# 6-User_IO.net
KiCad netlist of a schematic drawn in Altium Designer
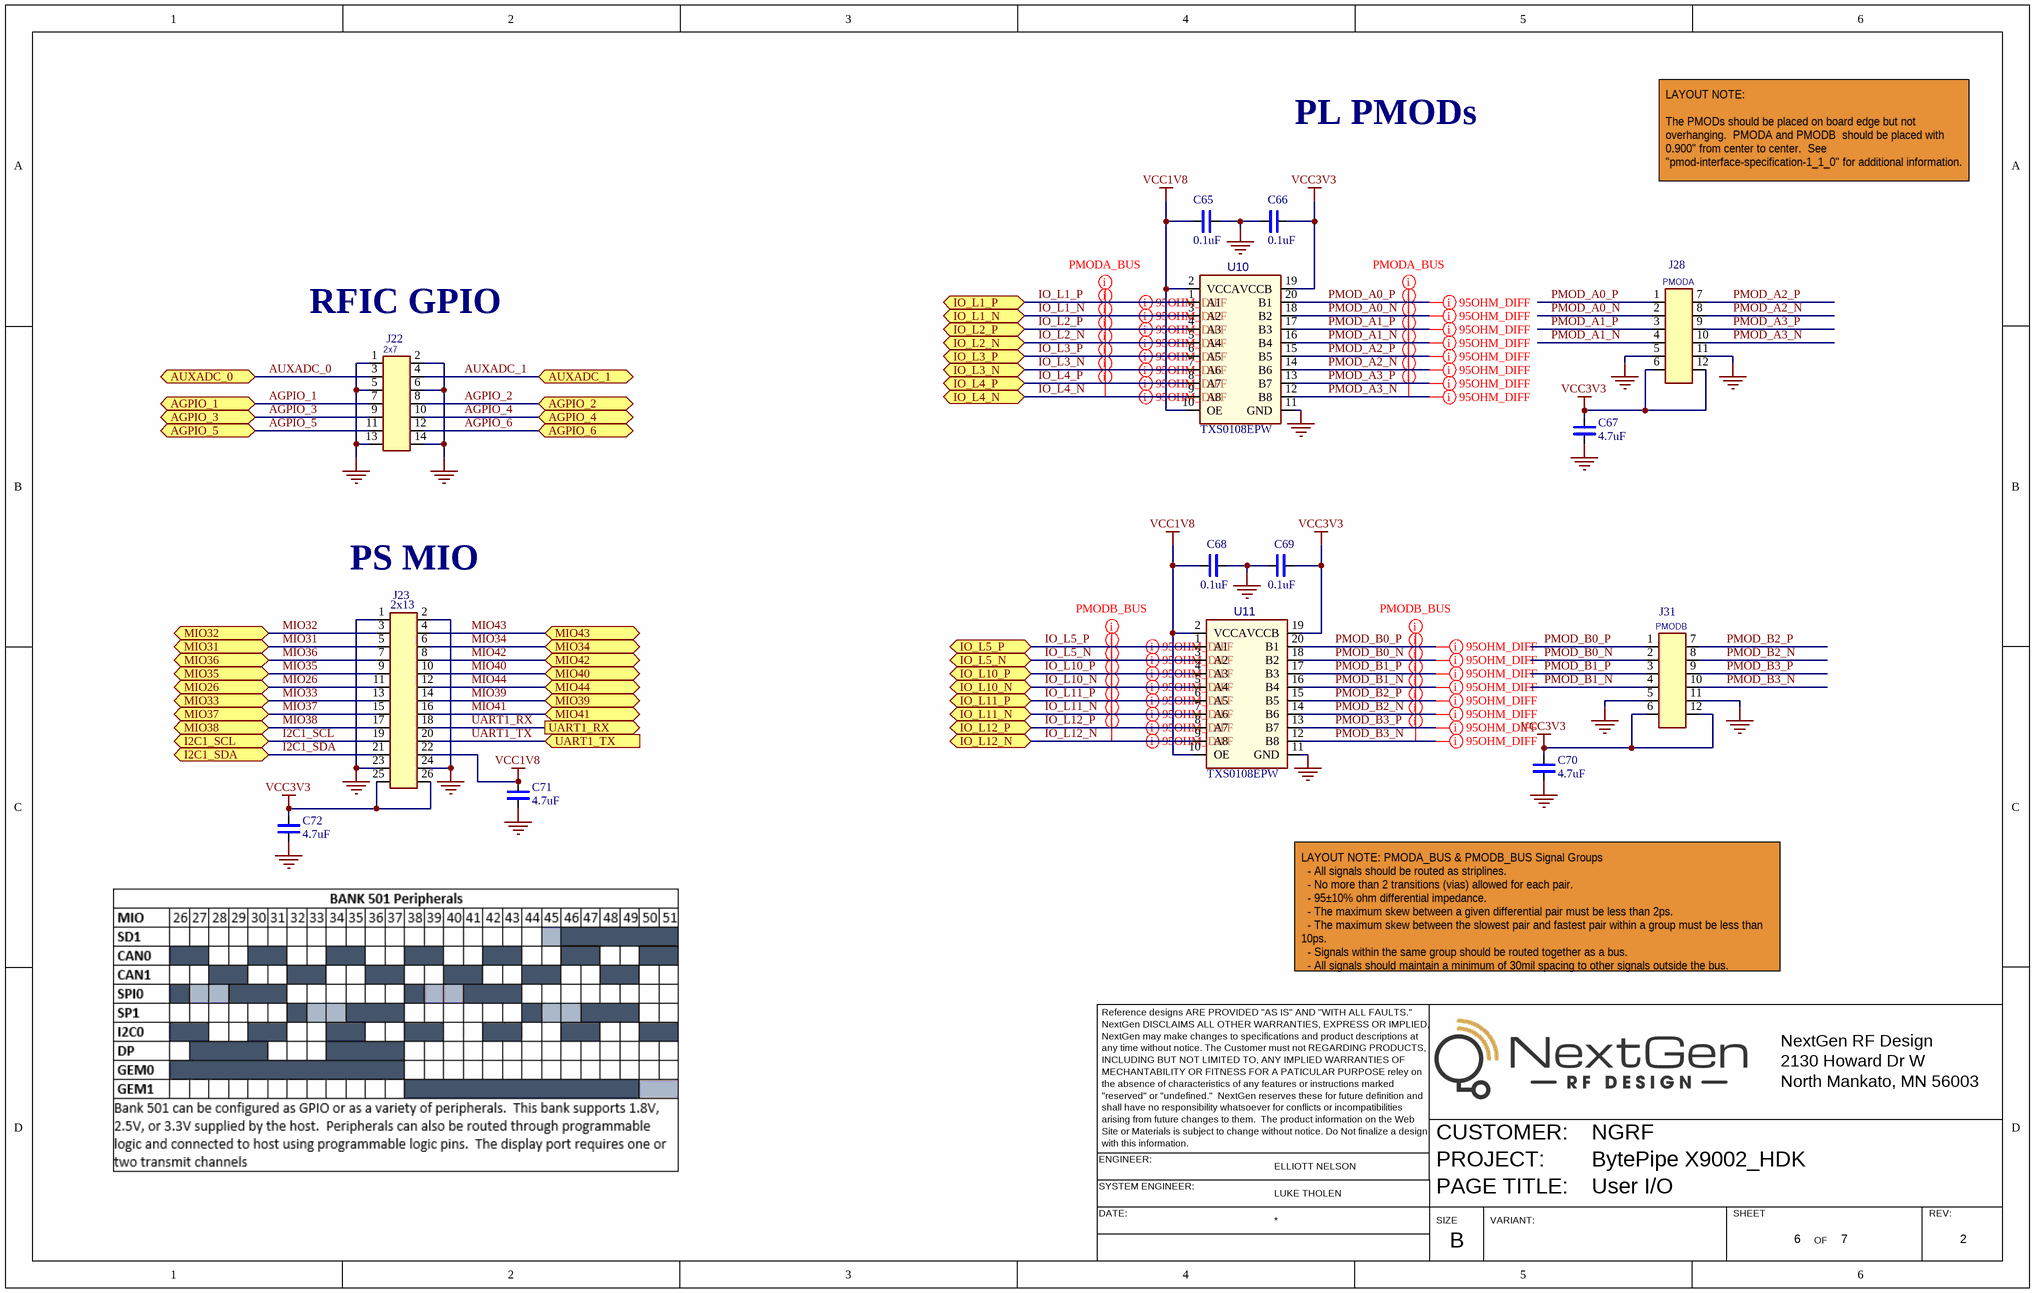
[diagram p0: 6-User IO.SchDoc]

(export (version "E")
  (design (tool "Eeschema 10.0.6"))
  (components
    (comp (ref "C65")
      (value "0.1uF")
      (footprint "SM/0402/CAP")
      (description "CAP CER 0.1UF 25V X7R 0402")
      (fields (field (name "Comment") "CAP_CERAMIC_0402"))
      (libsource (lib "NextGenRF_Symbols_SMT") (part "CAP_CERAMIC_0402"))
    )
    (comp (ref "C66")
      (value "0.1uF")
      (footprint "SM/0402/CAP")
      (description "CAP CER 0.1UF 25V X7R 0402")
      (fields (field (name "Comment") "CAP_CERAMIC_0402"))
      (libsource (lib "NextGenRF_Symbols_SMT") (part "CAP_CERAMIC_0402"))
    )
    (comp (ref "C67")
      (value "4.7uF")
      (footprint "SM/0402/CAP")
      (description "CAP CER 4.7UF 10V X5R 0402")
      (fields (field (name "Comment") "CAP_CERAMIC_0402"))
      (libsource (lib "NextGenRF_Symbols_SMT") (part "CAP_CERAMIC_0402"))
    )
    (comp (ref "C68")
      (value "0.1uF")
      (footprint "SM/0402/CAP")
      (description "CAP CER 0.1UF 25V X7R 0402")
      (fields (field (name "Comment") "CAP_CERAMIC_0402"))
      (libsource (lib "NextGenRF_Symbols_SMT") (part "CAP_CERAMIC_0402"))
    )
    (comp (ref "C69")
      (value "0.1uF")
      (footprint "SM/0402/CAP")
      (description "CAP CER 0.1UF 25V X7R 0402")
      (fields (field (name "Comment") "CAP_CERAMIC_0402"))
      (libsource (lib "NextGenRF_Symbols_SMT") (part "CAP_CERAMIC_0402"))
    )
    (comp (ref "C70")
      (value "4.7uF")
      (footprint "SM/0402/CAP")
      (description "CAP CER 4.7UF 10V X5R 0402")
      (fields (field (name "Comment") "CAP_CERAMIC_0402"))
      (libsource (lib "NextGenRF_Symbols_SMT") (part "CAP_CERAMIC_0402"))
    )
    (comp (ref "C71")
      (value "4.7uF")
      (footprint "SM/0402/CAP")
      (description "CAP CER 4.7UF 10V X5R 0402")
      (fields (field (name "Comment") "CAP_CERAMIC_0402"))
      (libsource (lib "NextGenRF_Symbols_SMT") (part "CAP_CERAMIC_0402"))
    )
    (comp (ref "C72")
      (value "4.7uF")
      (footprint "SM/0402/CAP")
      (description "CAP CER 4.7UF 10V X5R 0402")
      (fields (field (name "Comment") "CAP_CERAMIC_0402"))
      (libsource (lib "NextGenRF_Symbols_SMT") (part "CAP_CERAMIC_0402"))
    )
    (comp (ref "J22")
      (value "2x7")
      (footprint "CON/100SP/2X7P/VT/038_A")
      (description "Connector Header Through Hole 14 position 0.100\" (2.54mm)")
      (fields (field (name "Comment") "CON_100SP_2X7P_VT"))
      (libsource (lib "NextGenRF_Symbols_TH") (part "CON_100SP_2X7P_VT"))
    )
    (comp (ref "J23")
      (value "2x13")
      (footprint "NGRF_Thru-Hole_Footprints:CON/100SP/2X13P/038_A")
      (description "PIN HEADER, DOUBLE ROW 26 PIN, S")
      (fields (field (name "Comment") "CON_100SP_2X13P_VERT"))
      (libsource (lib "NextGenRF_Symbols_TH") (part "CON_100SP_2X13P_VERT"))
    )
    (comp (ref "J28")
      (value "PMODA")
      (footprint "CON/SAMTEC/SSW/2X6/RA_A/PMOD")
      (description "Header, 100 mil, 2x6, Right Angle, PMOD pin out.")
      (fields (field (name "Comment") "CON_100SP_2X6P_RA_PMOD"))
      (libsource (lib "NextGenRF_Symbols_TH") (part "CON_100SP_2X6P_RA_PMOD"))
    )
    (comp (ref "J31")
      (value "PMODB")
      (footprint "CON/SAMTEC/SSW/2X6/RA_A/PMOD")
      (description "Header, 100 mil, 2x6, Right Angle, PMOD pin out.")
      (fields (field (name "Comment") "CON_100SP_2X6P_RA_PMOD"))
      (libsource (lib "NextGenRF_Symbols_TH") (part "CON_100SP_2X6P_RA_PMOD"))
    )
    (comp (ref "U10")
      (value "TXS0108EPW")
      (footprint "SM/TSSOP20_6.5X6.4MM")
      (description "IC TRNSLTR BIDIRECTIONAL 20VQFN")
      (fields (field (name "Comment") "IC_TXS0108_TSSOP-20"))
      (libsource (lib "NextGenRF_Symbols_SMT") (part "IC_TXS0108_TSSOP-20"))
    )
    (comp (ref "U11")
      (value "TXS0108EPW")
      (footprint "SM/TSSOP20_6.5X6.4MM")
      (description "IC TRNSLTR BIDIRECTIONAL 20VQFN")
      (fields (field (name "Comment") "IC_TXS0108_TSSOP-20"))
      (libsource (lib "NextGenRF_Symbols_SMT") (part "IC_TXS0108_TSSOP-20"))
    )
  )
  (nets
    (net (code "1") (name "/AGPIO_1") (class "Default")
      (node (ref "J22") (pin "7") (pinfunction "N7_7") (pintype "passive"))
    )
    (net (code "2") (name "/AGPIO_2") (class "Default")
      (node (ref "J22") (pin "8") (pinfunction "N8_8") (pintype "passive"))
    )
    (net (code "3") (name "/AGPIO_3") (class "Default")
      (node (ref "J22") (pin "9") (pinfunction "N9_9") (pintype "passive"))
    )
    (net (code "4") (name "/AGPIO_4") (class "Default")
      (node (ref "J22") (pin "10") (pinfunction "N10_10") (pintype "passive"))
    )
    (net (code "5") (name "/AGPIO_5") (class "Default")
      (node (ref "J22") (pin "11") (pinfunction "N11_11") (pintype "passive"))
    )
    (net (code "6") (name "/AGPIO_6") (class "Default")
      (node (ref "J22") (pin "12") (pinfunction "N12_12") (pintype "passive"))
    )
    (net (code "7") (name "/AUXADC_0") (class "Default")
      (node (ref "J22") (pin "3") (pinfunction "N3_3") (pintype "passive"))
    )
    (net (code "8") (name "/AUXADC_1") (class "Default")
      (node (ref "J22") (pin "4") (pinfunction "N4_4") (pintype "passive"))
    )
    (net (code "9") (name "/I2C1_SCL") (class "Default")
      (node (ref "J23") (pin "19") (pinfunction "N19_19") (pintype "passive"))
    )
    (net (code "10") (name "/I2C1_SDA") (class "Default")
      (node (ref "J23") (pin "21") (pinfunction "N21_21") (pintype "passive"))
    )
    (net (code "11") (name "/IO_L1_N") (class "Default")
      (node (ref "U10") (pin "3") (pinfunction "A2_3") (pintype "passive"))
    )
    (net (code "12") (name "/IO_L1_P") (class "Default")
      (node (ref "U10") (pin "1") (pinfunction "A1_1") (pintype "passive"))
    )
    (net (code "13") (name "/IO_L2_N") (class "Default")
      (node (ref "U10") (pin "5") (pinfunction "A4_5") (pintype "passive"))
    )
    (net (code "14") (name "/IO_L2_P") (class "Default")
      (node (ref "U10") (pin "4") (pinfunction "A3_4") (pintype "passive"))
    )
    (net (code "15") (name "/IO_L3_N") (class "Default")
      (node (ref "U10") (pin "7") (pinfunction "A6_7") (pintype "passive"))
    )
    (net (code "16") (name "/IO_L3_P") (class "Default")
      (node (ref "U10") (pin "6") (pinfunction "A5_6") (pintype "passive"))
    )
    (net (code "17") (name "/IO_L4_N") (class "Default")
      (node (ref "U10") (pin "9") (pinfunction "A8_9") (pintype "passive"))
    )
    (net (code "18") (name "/IO_L4_P") (class "Default")
      (node (ref "U10") (pin "8") (pinfunction "A7_8") (pintype "passive"))
    )
    (net (code "19") (name "/IO_L5_N") (class "Default")
      (node (ref "U11") (pin "3") (pinfunction "A2_3") (pintype "passive"))
    )
    (net (code "20") (name "/IO_L5_P") (class "Default")
      (node (ref "U11") (pin "1") (pinfunction "A1_1") (pintype "passive"))
    )
    (net (code "21") (name "/IO_L10_N") (class "Default")
      (node (ref "U11") (pin "5") (pinfunction "A4_5") (pintype "passive"))
    )
    (net (code "22") (name "/IO_L10_P") (class "Default")
      (node (ref "U11") (pin "4") (pinfunction "A3_4") (pintype "passive"))
    )
    (net (code "23") (name "/IO_L11_N") (class "Default")
      (node (ref "U11") (pin "7") (pinfunction "A6_7") (pintype "passive"))
    )
    (net (code "24") (name "/IO_L11_P") (class "Default")
      (node (ref "U11") (pin "6") (pinfunction "A5_6") (pintype "passive"))
    )
    (net (code "25") (name "/IO_L12_N") (class "Default")
      (node (ref "U11") (pin "9") (pinfunction "A8_9") (pintype "passive"))
    )
    (net (code "26") (name "/IO_L12_P") (class "Default")
      (node (ref "U11") (pin "8") (pinfunction "A7_8") (pintype "passive"))
    )
    (net (code "27") (name "/MIO26") (class "Default")
      (node (ref "J23") (pin "11") (pinfunction "N11_11") (pintype "passive"))
    )
    (net (code "28") (name "/MIO31") (class "Default")
      (node (ref "J23") (pin "5") (pinfunction "N5_5") (pintype "passive"))
    )
    (net (code "29") (name "/MIO32") (class "Default")
      (node (ref "J23") (pin "3") (pinfunction "N3_3") (pintype "passive"))
    )
    (net (code "30") (name "/MIO33") (class "Default")
      (node (ref "J23") (pin "13") (pinfunction "N13_13") (pintype "passive"))
    )
    (net (code "31") (name "/MIO34") (class "Default")
      (node (ref "J23") (pin "6") (pinfunction "N6_6") (pintype "passive"))
    )
    (net (code "32") (name "/MIO35") (class "Default")
      (node (ref "J23") (pin "9") (pinfunction "N9_9") (pintype "passive"))
    )
    (net (code "33") (name "/MIO36") (class "Default")
      (node (ref "J23") (pin "7") (pinfunction "N7_7") (pintype "passive"))
    )
    (net (code "34") (name "/MIO37") (class "Default")
      (node (ref "J23") (pin "15") (pinfunction "N15_15") (pintype "passive"))
    )
    (net (code "35") (name "/MIO38") (class "Default")
      (node (ref "J23") (pin "17") (pinfunction "N17_17") (pintype "passive"))
    )
    (net (code "36") (name "/MIO39") (class "Default")
      (node (ref "J23") (pin "14") (pinfunction "N14_14") (pintype "passive"))
    )
    (net (code "37") (name "/MIO40") (class "Default")
      (node (ref "J23") (pin "10") (pinfunction "N10_10") (pintype "passive"))
    )
    (net (code "38") (name "/MIO41") (class "Default")
      (node (ref "J23") (pin "16") (pinfunction "N16_16") (pintype "passive"))
    )
    (net (code "39") (name "/MIO42") (class "Default")
      (node (ref "J23") (pin "8") (pinfunction "N8_8") (pintype "passive"))
    )
    (net (code "40") (name "/MIO43") (class "Default")
      (node (ref "J23") (pin "4") (pinfunction "N4_4") (pintype "passive"))
    )
    (net (code "41") (name "/MIO44") (class "Default")
      (node (ref "J23") (pin "12") (pinfunction "N12_12") (pintype "passive"))
    )
    (net (code "42") (name "/PMOD_A0_N") (class "Default")
      (node (ref "J28") (pin "2") (pinfunction "N2_2") (pintype "passive"))
      (node (ref "U10") (pin "18") (pinfunction "B2_18") (pintype "passive"))
    )
    (net (code "43") (name "/PMOD_A0_P") (class "Default")
      (node (ref "J28") (pin "1") (pinfunction "N1_1") (pintype "passive"))
      (node (ref "U10") (pin "20") (pinfunction "B1_20") (pintype "passive"))
    )
    (net (code "44") (name "/PMOD_A1_N") (class "Default")
      (node (ref "J28") (pin "4") (pinfunction "N4_4") (pintype "passive"))
      (node (ref "U10") (pin "16") (pinfunction "B4_16") (pintype "passive"))
    )
    (net (code "45") (name "/PMOD_A1_P") (class "Default")
      (node (ref "J28") (pin "3") (pinfunction "N3_3") (pintype "passive"))
      (node (ref "U10") (pin "17") (pinfunction "B3_17") (pintype "passive"))
    )
    (net (code "46") (name "/PMOD_A2_N") (class "Default")
      (node (ref "J28") (pin "8") (pinfunction "N8_8") (pintype "passive"))
      (node (ref "U10") (pin "14") (pinfunction "B6_14") (pintype "passive"))
    )
    (net (code "47") (name "/PMOD_A2_P") (class "Default")
      (node (ref "J28") (pin "7") (pinfunction "N7_7") (pintype "passive"))
      (node (ref "U10") (pin "15") (pinfunction "B5_15") (pintype "passive"))
    )
    (net (code "48") (name "/PMOD_A3_N") (class "Default")
      (node (ref "J28") (pin "10") (pinfunction "N10_10") (pintype "passive"))
      (node (ref "U10") (pin "12") (pinfunction "B8_12") (pintype "passive"))
    )
    (net (code "49") (name "/PMOD_A3_P") (class "Default")
      (node (ref "J28") (pin "9") (pinfunction "N9_9") (pintype "passive"))
      (node (ref "U10") (pin "13") (pinfunction "B7_13") (pintype "passive"))
    )
    (net (code "50") (name "/PMOD_B0_N") (class "Default")
      (node (ref "J31") (pin "2") (pinfunction "N2_2") (pintype "passive"))
      (node (ref "U11") (pin "18") (pinfunction "B2_18") (pintype "passive"))
    )
    (net (code "51") (name "/PMOD_B0_P") (class "Default")
      (node (ref "J31") (pin "1") (pinfunction "N1_1") (pintype "passive"))
      (node (ref "U11") (pin "20") (pinfunction "B1_20") (pintype "passive"))
    )
    (net (code "52") (name "/PMOD_B1_N") (class "Default")
      (node (ref "J31") (pin "4") (pinfunction "N4_4") (pintype "passive"))
      (node (ref "U11") (pin "16") (pinfunction "B4_16") (pintype "passive"))
    )
    (net (code "53") (name "/PMOD_B1_P") (class "Default")
      (node (ref "J31") (pin "3") (pinfunction "N3_3") (pintype "passive"))
      (node (ref "U11") (pin "17") (pinfunction "B3_17") (pintype "passive"))
    )
    (net (code "54") (name "/PMOD_B2_N") (class "Default")
      (node (ref "J31") (pin "8") (pinfunction "N8_8") (pintype "passive"))
      (node (ref "U11") (pin "14") (pinfunction "B6_14") (pintype "passive"))
    )
    (net (code "55") (name "/PMOD_B2_P") (class "Default")
      (node (ref "J31") (pin "7") (pinfunction "N7_7") (pintype "passive"))
      (node (ref "U11") (pin "15") (pinfunction "B5_15") (pintype "passive"))
    )
    (net (code "56") (name "/PMOD_B3_N") (class "Default")
      (node (ref "J31") (pin "10") (pinfunction "N10_10") (pintype "passive"))
      (node (ref "U11") (pin "12") (pinfunction "B8_12") (pintype "passive"))
    )
    (net (code "57") (name "/PMOD_B3_P") (class "Default")
      (node (ref "J31") (pin "9") (pinfunction "N9_9") (pintype "passive"))
      (node (ref "U11") (pin "13") (pinfunction "B7_13") (pintype "passive"))
    )
    (net (code "58") (name "/UART1_RX") (class "Default")
      (node (ref "J23") (pin "18") (pinfunction "N18_18") (pintype "passive"))
    )
    (net (code "59") (name "/UART1_TX") (class "Default")
      (node (ref "J23") (pin "20") (pinfunction "N20_20") (pintype "passive"))
    )
    (net (code "60") (name "GND") (class "Default")
      (node (ref "C65") (pin "2") (pinfunction "N2_2") (pintype "passive"))
      (node (ref "C66") (pin "1") (pinfunction "N1_1") (pintype "passive"))
      (node (ref "C67") (pin "2") (pinfunction "N2_2") (pintype "passive"))
      (node (ref "C68") (pin "2") (pinfunction "N2_2") (pintype "passive"))
      (node (ref "C69") (pin "1") (pinfunction "N1_1") (pintype "passive"))
      (node (ref "C70") (pin "2") (pinfunction "N2_2") (pintype "passive"))
      (node (ref "C71") (pin "2") (pinfunction "N2_2") (pintype "passive"))
      (node (ref "C72") (pin "2") (pinfunction "N2_2") (pintype "passive"))
      (node (ref "J22") (pin "1") (pinfunction "N1_1") (pintype "passive"))
      (node (ref "J22") (pin "13") (pinfunction "N13_13") (pintype "passive"))
      (node (ref "J22") (pin "14") (pinfunction "N14_14") (pintype "passive"))
      (node (ref "J22") (pin "2") (pinfunction "N2_2") (pintype "passive"))
      (node (ref "J22") (pin "5") (pinfunction "N5_5") (pintype "passive"))
      (node (ref "J22") (pin "6") (pinfunction "N6_6") (pintype "passive"))
      (node (ref "J23") (pin "1") (pinfunction "N1_1") (pintype "passive"))
      (node (ref "J23") (pin "2") (pinfunction "N2_2") (pintype "passive"))
      (node (ref "J23") (pin "23") (pinfunction "N23_23") (pintype "passive"))
      (node (ref "J23") (pin "24") (pinfunction "N24_24") (pintype "passive"))
      (node (ref "J28") (pin "11") (pinfunction "N11_11") (pintype "passive"))
      (node (ref "J28") (pin "5") (pinfunction "N5_5") (pintype "passive"))
      (node (ref "J31") (pin "11") (pinfunction "N11_11") (pintype "passive"))
      (node (ref "J31") (pin "5") (pinfunction "N5_5") (pintype "passive"))
      (node (ref "U10") (pin "11") (pinfunction "GND_11") (pintype "passive"))
      (node (ref "U11") (pin "11") (pinfunction "GND_11") (pintype "passive"))
    )
    (net (code "61") (name "VCC1V8") (class "Default")
      (node (ref "C65") (pin "1") (pinfunction "N1_1") (pintype "passive"))
      (node (ref "C68") (pin "1") (pinfunction "N1_1") (pintype "passive"))
      (node (ref "C71") (pin "1") (pinfunction "N1_1") (pintype "passive"))
      (node (ref "J23") (pin "22") (pinfunction "N22_22") (pintype "passive"))
      (node (ref "U10") (pin "10") (pinfunction "OE_10") (pintype "passive"))
      (node (ref "U10") (pin "2") (pinfunction "VCCA_2") (pintype "passive"))
      (node (ref "U11") (pin "10") (pinfunction "OE_10") (pintype "passive"))
      (node (ref "U11") (pin "2") (pinfunction "VCCA_2") (pintype "passive"))
    )
    (net (code "62") (name "VCC3V3") (class "Default")
      (node (ref "C66") (pin "2") (pinfunction "N2_2") (pintype "passive"))
      (node (ref "C67") (pin "1") (pinfunction "N1_1") (pintype "passive"))
      (node (ref "C69") (pin "2") (pinfunction "N2_2") (pintype "passive"))
      (node (ref "C70") (pin "1") (pinfunction "N1_1") (pintype "passive"))
      (node (ref "C72") (pin "1") (pinfunction "N1_1") (pintype "passive"))
      (node (ref "J23") (pin "25") (pinfunction "N25_25") (pintype "passive"))
      (node (ref "J23") (pin "26") (pinfunction "N26_26") (pintype "passive"))
      (node (ref "J28") (pin "12") (pinfunction "N12_12") (pintype "passive"))
      (node (ref "J28") (pin "6") (pinfunction "N6_6") (pintype "passive"))
      (node (ref "J31") (pin "12") (pinfunction "N12_12") (pintype "passive"))
      (node (ref "J31") (pin "6") (pinfunction "N6_6") (pintype "passive"))
      (node (ref "U10") (pin "19") (pinfunction "VCCB_19") (pintype "passive"))
      (node (ref "U11") (pin "19") (pinfunction "VCCB_19") (pintype "passive"))
    )
  )
)
